# i2c_adc_avr_inline_soic.net
KiCad netlist of a schematic drawn in EAGLE
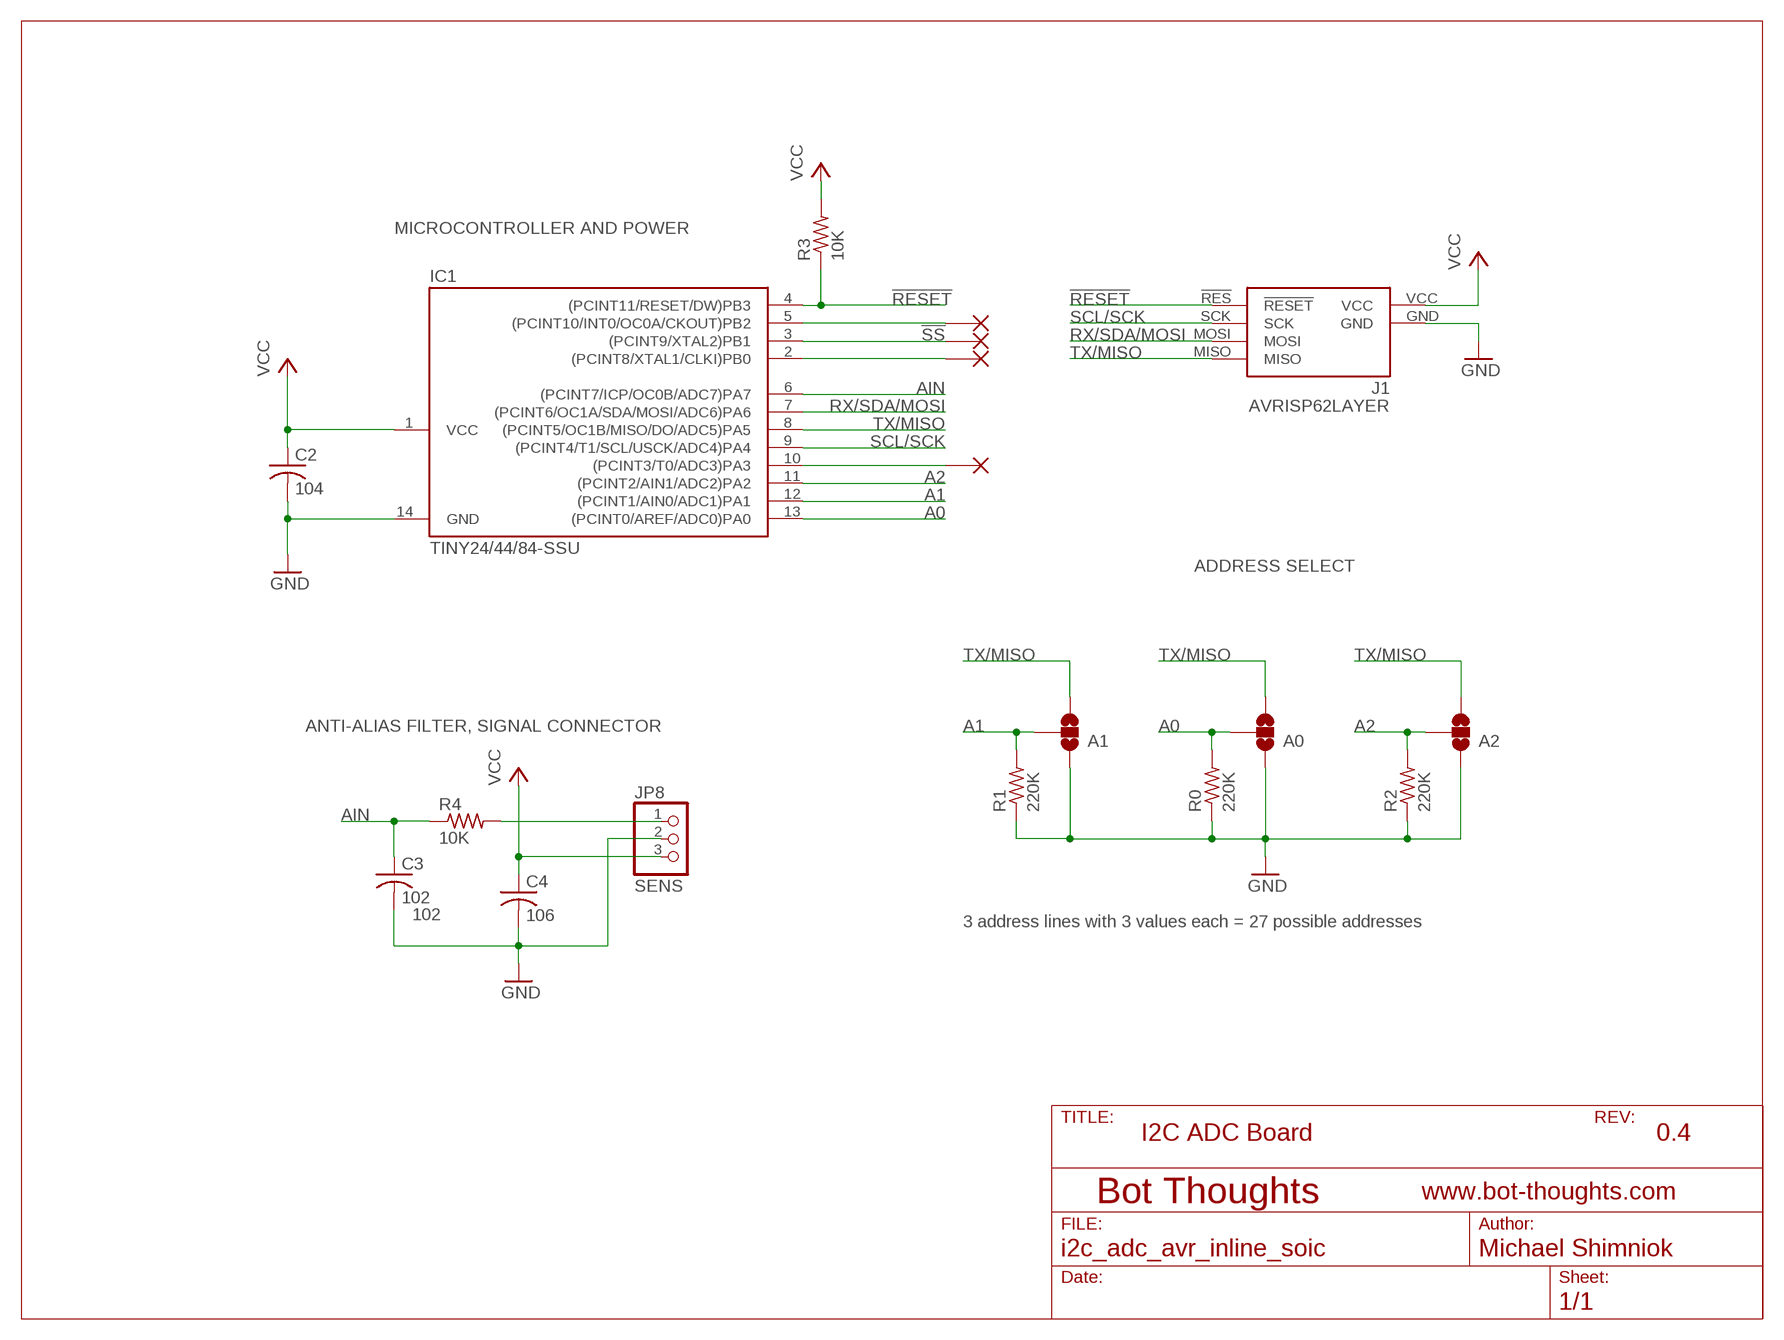
[diagram p0: schematic, sheet 1]

(export (version "E")
  (design (tool "Eeschema 10.0.6"))
  (components
    (comp (ref "A0")
      (value "SOLDERJUMPER_2WAYS")
      (footprint "eagle-import:SJ_3")
      (libsource (lib "eagle-import") (part "SOLDERJUMPER_2WAYS"))
    )
    (comp (ref "A1")
      (value "SOLDERJUMPER_2WAYS")
      (footprint "eagle-import:SJ_3")
      (libsource (lib "eagle-import") (part "SOLDERJUMPER_2WAYS"))
    )
    (comp (ref "A2")
      (value "SOLDERJUMPER_2WAYS")
      (footprint "eagle-import:SJ_3")
      (libsource (lib "eagle-import") (part "SOLDERJUMPER_2WAYS"))
    )
    (comp (ref "C2")
      (value "104")
      (footprint "eagle-import:C0603")
      (fields (field (name "PARTNO") "C1608X7R1E104K080AA"))
      (libsource (lib "eagle-import") (part "C-USC0603"))
    )
    (comp (ref "C3")
      (value "102")
      (footprint "eagle-import:C0603")
      (fields (field (name "CODE") "102") (field (name "PARTNO") "CL10B102KB8SFNC"))
      (libsource (lib "eagle-import") (part "C-USC0603"))
    )
    (comp (ref "C4")
      (value "106")
      (footprint "eagle-import:C0603")
      (fields (field (name "PARTNO") "CL10A106MP8NNNC"))
      (libsource (lib "eagle-import") (part "C-USC0603"))
    )
    (comp (ref "IC1")
      (value "TINY24/44/84-SSU")
      (footprint "eagle-import:SOIC14")
      (libsource (lib "eagle-import") (part "TINY24/44/84-SSU"))
    )
    (comp (ref "J1")
      (value "AVRISP62LAYER")
      (footprint "eagle-import:2X3_2LAYER")
      (libsource (lib "eagle-import") (part "AVRISP62LAYER"))
    )
    (comp (ref "JP8")
      (value "SENS")
      (footprint "eagle-import:1X03-S")
      (libsource (lib "eagle-import") (part "PINHD-1X03_2.54-S"))
    )
    (comp (ref "R0")
      (value "220K")
      (footprint "eagle-import:R0603")
      (fields (field (name "PARTNO") "RC1608J224CS"))
      (libsource (lib "eagle-import") (part "R-US_R0603"))
    )
    (comp (ref "R1")
      (value "220K")
      (footprint "eagle-import:R0603")
      (fields (field (name "PARTNO") "RC1608J224CS"))
      (libsource (lib "eagle-import") (part "R-US_R0603"))
    )
    (comp (ref "R2")
      (value "220K")
      (footprint "eagle-import:R0603")
      (fields (field (name "PARTNO") "RC1608J224CS"))
      (libsource (lib "eagle-import") (part "R-US_R0603"))
    )
    (comp (ref "R3")
      (value "10K")
      (footprint "eagle-import:R0603")
      (fields (field (name "PARTNO") "1622829-1"))
      (libsource (lib "eagle-import") (part "R-US_R0603"))
    )
    (comp (ref "R4")
      (value "10K")
      (footprint "eagle-import:R0603")
      (fields (field (name "PARTNO") "1622829-1"))
      (libsource (lib "eagle-import") (part "R-US_R0603"))
    )
    (comp (ref "X1")
      (value "PB2")
      (footprint "eagle-import:PAD0.07X0.15")
      (libsource (lib "eagle-import") (part "PINPADSMD0.07X0.15"))
    )
    (comp (ref "X2")
      (value "!SS")
      (footprint "eagle-import:PAD0.07X0.15")
      (libsource (lib "eagle-import") (part "PINPADSMD0.07X0.15"))
    )
    (comp (ref "X3")
      (value "PB0")
      (footprint "eagle-import:PAD0.07X0.15")
      (libsource (lib "eagle-import") (part "PINPADSMD0.07X0.15"))
    )
    (comp (ref "X4")
      (value "PA3")
      (footprint "eagle-import:PAD0.07X0.15")
      (libsource (lib "eagle-import") (part "PINPADSMD0.07X0.15"))
    )
  )
  (nets
    (net (code "1") (name "/A0") (class "Default")
      (node (ref "A0") (pin "2") (pinfunction "2_2") (pintype "passive"))
      (node (ref "IC1") (pin "13") (pinfunction "(PCINT0/AREF/ADC0)PA0_13") (pintype "bidirectional"))
      (node (ref "R0") (pin "2") (pinfunction "2_2") (pintype "passive"))
    )
    (net (code "2") (name "/A1") (class "Default")
      (node (ref "A1") (pin "2") (pinfunction "2_2") (pintype "passive"))
      (node (ref "IC1") (pin "12") (pinfunction "(PCINT1/AIN0/ADC1)PA1_12") (pintype "bidirectional"))
      (node (ref "R1") (pin "2") (pinfunction "2_2") (pintype "passive"))
    )
    (net (code "3") (name "/A2") (class "Default")
      (node (ref "A2") (pin "2") (pinfunction "2_2") (pintype "passive"))
      (node (ref "IC1") (pin "11") (pinfunction "(PCINT2/AIN1/ADC2)PA2_11") (pintype "bidirectional"))
      (node (ref "R2") (pin "2") (pinfunction "2_2") (pintype "passive"))
    )
    (net (code "4") (name "/AIN") (class "Default")
      (node (ref "C3") (pin "1") (pinfunction "1_1") (pintype "passive"))
      (node (ref "IC1") (pin "6") (pinfunction "(PCINT7/ICP/OC0B/ADC7)PA7_6") (pintype "bidirectional"))
      (node (ref "R4") (pin "1") (pinfunction "1_1") (pintype "passive"))
    )
    (net (code "5") (name "/RX{slash}SDA{slash}MOSI") (class "Default")
      (node (ref "IC1") (pin "7") (pinfunction "(PCINT6/OC1A/SDA/MOSI/ADC6)PA6_7") (pintype "bidirectional"))
      (node (ref "J1") (pin "MOSI") (pinfunction "MOSI_MOSI") (pintype "output"))
    )
    (net (code "6") (name "/SCL{slash}SCK") (class "Default")
      (node (ref "IC1") (pin "9") (pinfunction "(PCINT4/T1/SCL/USCK/ADC4)PA4_9") (pintype "bidirectional"))
      (node (ref "J1") (pin "SCK") (pinfunction "SCK_SCK") (pintype "output"))
    )
    (net (code "7") (name "/TX{slash}MISO") (class "Default")
      (node (ref "A0") (pin "3") (pinfunction "3_3") (pintype "passive"))
      (node (ref "A1") (pin "3") (pinfunction "3_3") (pintype "passive"))
      (node (ref "A2") (pin "3") (pinfunction "3_3") (pintype "passive"))
      (node (ref "IC1") (pin "8") (pinfunction "(PCINT5/OC1B/MISO/DO/ADC5)PA5_8") (pintype "bidirectional"))
      (node (ref "J1") (pin "MISO") (pinfunction "MISO_MISO") (pintype "input"))
    )
    (net (code "8") (name "/~{RESET}") (class "Default")
      (node (ref "IC1") (pin "4") (pinfunction "(PCINT11/RESET/DW)PB3_4") (pintype "bidirectional"))
      (node (ref "J1") (pin "!RES") (pinfunction "~{RESET}_!RES") (pintype "output"))
      (node (ref "R3") (pin "1") (pinfunction "1_1") (pintype "passive"))
    )
    (net (code "9") (name "/~{SS}") (class "Default")
      (node (ref "IC1") (pin "3") (pinfunction "(PCINT9/XTAL2)PB1_3") (pintype "bidirectional"))
      (node (ref "X2") (pin "P$1") (pinfunction "P$1_P$1") (pintype "bidirectional"))
    )
    (net (code "10") (name "GND") (class "Default")
      (node (ref "A0") (pin "1") (pinfunction "1_1") (pintype "passive"))
      (node (ref "A1") (pin "1") (pinfunction "1_1") (pintype "passive"))
      (node (ref "A2") (pin "1") (pinfunction "1_1") (pintype "passive"))
      (node (ref "C2") (pin "2") (pinfunction "2_2") (pintype "passive"))
      (node (ref "C3") (pin "2") (pinfunction "2_2") (pintype "passive"))
      (node (ref "C4") (pin "2") (pinfunction "2_2") (pintype "passive"))
      (node (ref "IC1") (pin "14") (pinfunction "GND_14") (pintype "power_in"))
      (node (ref "J1") (pin "GND") (pinfunction "GND_GND") (pintype "power_in"))
      (node (ref "JP8") (pin "2") (pinfunction "2_2") (pintype "passive"))
      (node (ref "R0") (pin "1") (pinfunction "1_1") (pintype "passive"))
      (node (ref "R1") (pin "1") (pinfunction "1_1") (pintype "passive"))
      (node (ref "R2") (pin "1") (pinfunction "1_1") (pintype "passive"))
    )
    (net (code "11") (name "Net-(IC1-(PCINT3{slash}T0{slash}ADC3)PA3)") (class "Default")
      (node (ref "IC1") (pin "10") (pinfunction "(PCINT3/T0/ADC3)PA3_10") (pintype "bidirectional"))
      (node (ref "X4") (pin "P$1") (pinfunction "P$1_P$1") (pintype "bidirectional"))
    )
    (net (code "12") (name "Net-(IC1-(PCINT8{slash}XTAL1{slash}CLKI)PB0)") (class "Default")
      (node (ref "IC1") (pin "2") (pinfunction "(PCINT8/XTAL1/CLKI)PB0_2") (pintype "bidirectional"))
      (node (ref "X3") (pin "P$1") (pinfunction "P$1_P$1") (pintype "bidirectional"))
    )
    (net (code "13") (name "Net-(IC1-(PCINT10{slash}INT0{slash}OC0A{slash}CKOUT)PB2)") (class "Default")
      (node (ref "IC1") (pin "5") (pinfunction "(PCINT10/INT0/OC0A/CKOUT)PB2_5") (pintype "bidirectional"))
      (node (ref "X1") (pin "P$1") (pinfunction "P$1_P$1") (pintype "bidirectional"))
    )
    (net (code "14") (name "Net-(JP8-Pad1)") (class "Default")
      (node (ref "JP8") (pin "1") (pinfunction "1_1") (pintype "passive"))
      (node (ref "R4") (pin "2") (pinfunction "2_2") (pintype "passive"))
    )
    (net (code "15") (name "VCC") (class "Default")
      (node (ref "C2") (pin "1") (pinfunction "1_1") (pintype "passive"))
      (node (ref "C4") (pin "1") (pinfunction "1_1") (pintype "passive"))
      (node (ref "IC1") (pin "1") (pinfunction "VCC_1") (pintype "power_in"))
      (node (ref "J1") (pin "VCC") (pinfunction "VCC_VCC") (pintype "power_in"))
      (node (ref "JP8") (pin "3") (pinfunction "3_3") (pintype "passive"))
      (node (ref "R3") (pin "2") (pinfunction "2_2") (pintype "passive"))
    )
  )
)
